# DATN2022_Display.net
KiCad netlist of a schematic drawn in Altium Designer
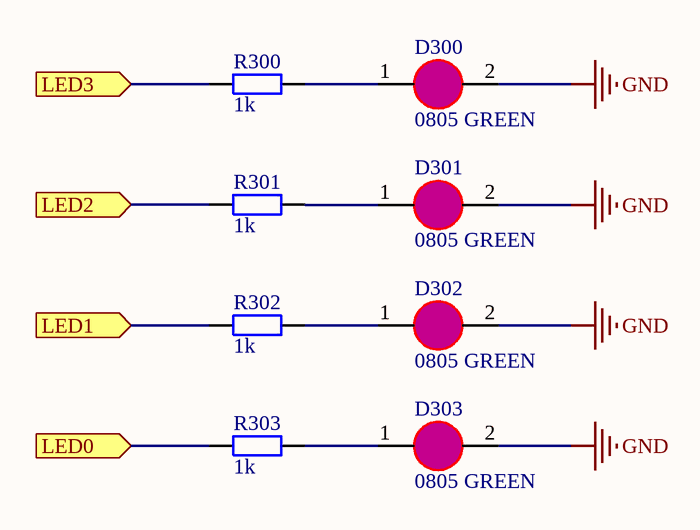
[diagram p0: DATN2022.Display.SchDoc]

(export (version "E")
  (design (tool "Eeschema 10.0.6"))
  (components
    (comp (ref "D300")
      (value "0805 GREEN")
      (footprint "LED_0805_GREEN")
      (description "LED SMD 0805")
      (libsource (lib "04.Diode_Led") (part "LED0805"))
    )
    (comp (ref "D301")
      (value "0805 GREEN")
      (footprint "LED_0805_GREEN")
      (description "LED SMD 0805")
      (libsource (lib "04.Diode_Led") (part "LED0805"))
    )
    (comp (ref "D302")
      (value "0805 GREEN")
      (footprint "LED_0805_GREEN")
      (description "LED SMD 0805")
      (libsource (lib "04.Diode_Led") (part "LED0805"))
    )
    (comp (ref "D303")
      (value "0805 GREEN")
      (footprint "LED_0805_GREEN")
      (description "LED SMD 0805")
      (libsource (lib "04.Diode_Led") (part "LED0805"))
    )
    (comp (ref "R300")
      (value "1k")
      (footprint "RES_0805(2012)")
      (description "Resistor SMD 0805")
      (fields (field (name "PUBLISHER") "Altium Limited"))
      (libsource (lib "02.Resistor") (part "R0805"))
    )
    (comp (ref "R301")
      (value "1k")
      (footprint "RES_0805(2012)")
      (description "Resistor SMD 0805")
      (fields (field (name "PUBLISHER") "Altium Limited"))
      (libsource (lib "02.Resistor") (part "R0805"))
    )
    (comp (ref "R302")
      (value "1k")
      (footprint "RES_0805(2012)")
      (description "Resistor SMD 0805")
      (fields (field (name "PUBLISHER") "Altium Limited"))
      (libsource (lib "02.Resistor") (part "R0805"))
    )
    (comp (ref "R303")
      (value "1k")
      (footprint "RES_0805(2012)")
      (description "Resistor SMD 0805")
      (fields (field (name "PUBLISHER") "Altium Limited"))
      (libsource (lib "02.Resistor") (part "R0805"))
    )
  )
  (nets
    (net (code "1") (name "/LED0") (class "Default")
      (node (ref "R303") (pin "1") (pinfunction "1_1") (pintype "passive"))
    )
    (net (code "2") (name "/LED1") (class "Default")
      (node (ref "R302") (pin "1") (pinfunction "1_1") (pintype "passive"))
    )
    (net (code "3") (name "/LED2") (class "Default")
      (node (ref "R301") (pin "1") (pinfunction "1_1") (pintype "passive"))
    )
    (net (code "4") (name "/LED3") (class "Default")
      (node (ref "R300") (pin "1") (pinfunction "1_1") (pintype "passive"))
    )
    (net (code "5") (name "GND") (class "Default")
      (node (ref "D300") (pin "2") (pinfunction "K_2") (pintype "passive"))
      (node (ref "D301") (pin "2") (pinfunction "K_2") (pintype "passive"))
      (node (ref "D302") (pin "2") (pinfunction "K_2") (pintype "passive"))
      (node (ref "D303") (pin "2") (pinfunction "K_2") (pintype "passive"))
    )
    (net (code "6") (name "Net-(D300-A)") (class "Default")
      (node (ref "D300") (pin "1") (pinfunction "A_1") (pintype "passive"))
      (node (ref "R300") (pin "2") (pinfunction "2_2") (pintype "passive"))
    )
    (net (code "7") (name "Net-(D301-A)") (class "Default")
      (node (ref "D301") (pin "1") (pinfunction "A_1") (pintype "passive"))
      (node (ref "R301") (pin "2") (pinfunction "2_2") (pintype "passive"))
    )
    (net (code "8") (name "Net-(D302-A)") (class "Default")
      (node (ref "D302") (pin "1") (pinfunction "A_1") (pintype "passive"))
      (node (ref "R302") (pin "2") (pinfunction "2_2") (pintype "passive"))
    )
    (net (code "9") (name "Net-(D303-A)") (class "Default")
      (node (ref "D303") (pin "1") (pinfunction "A_1") (pintype "passive"))
      (node (ref "R303") (pin "2") (pinfunction "2_2") (pintype "passive"))
    )
  )
)
